# JL2.net
KiCad netlist of a schematic drawn in Altium Designer
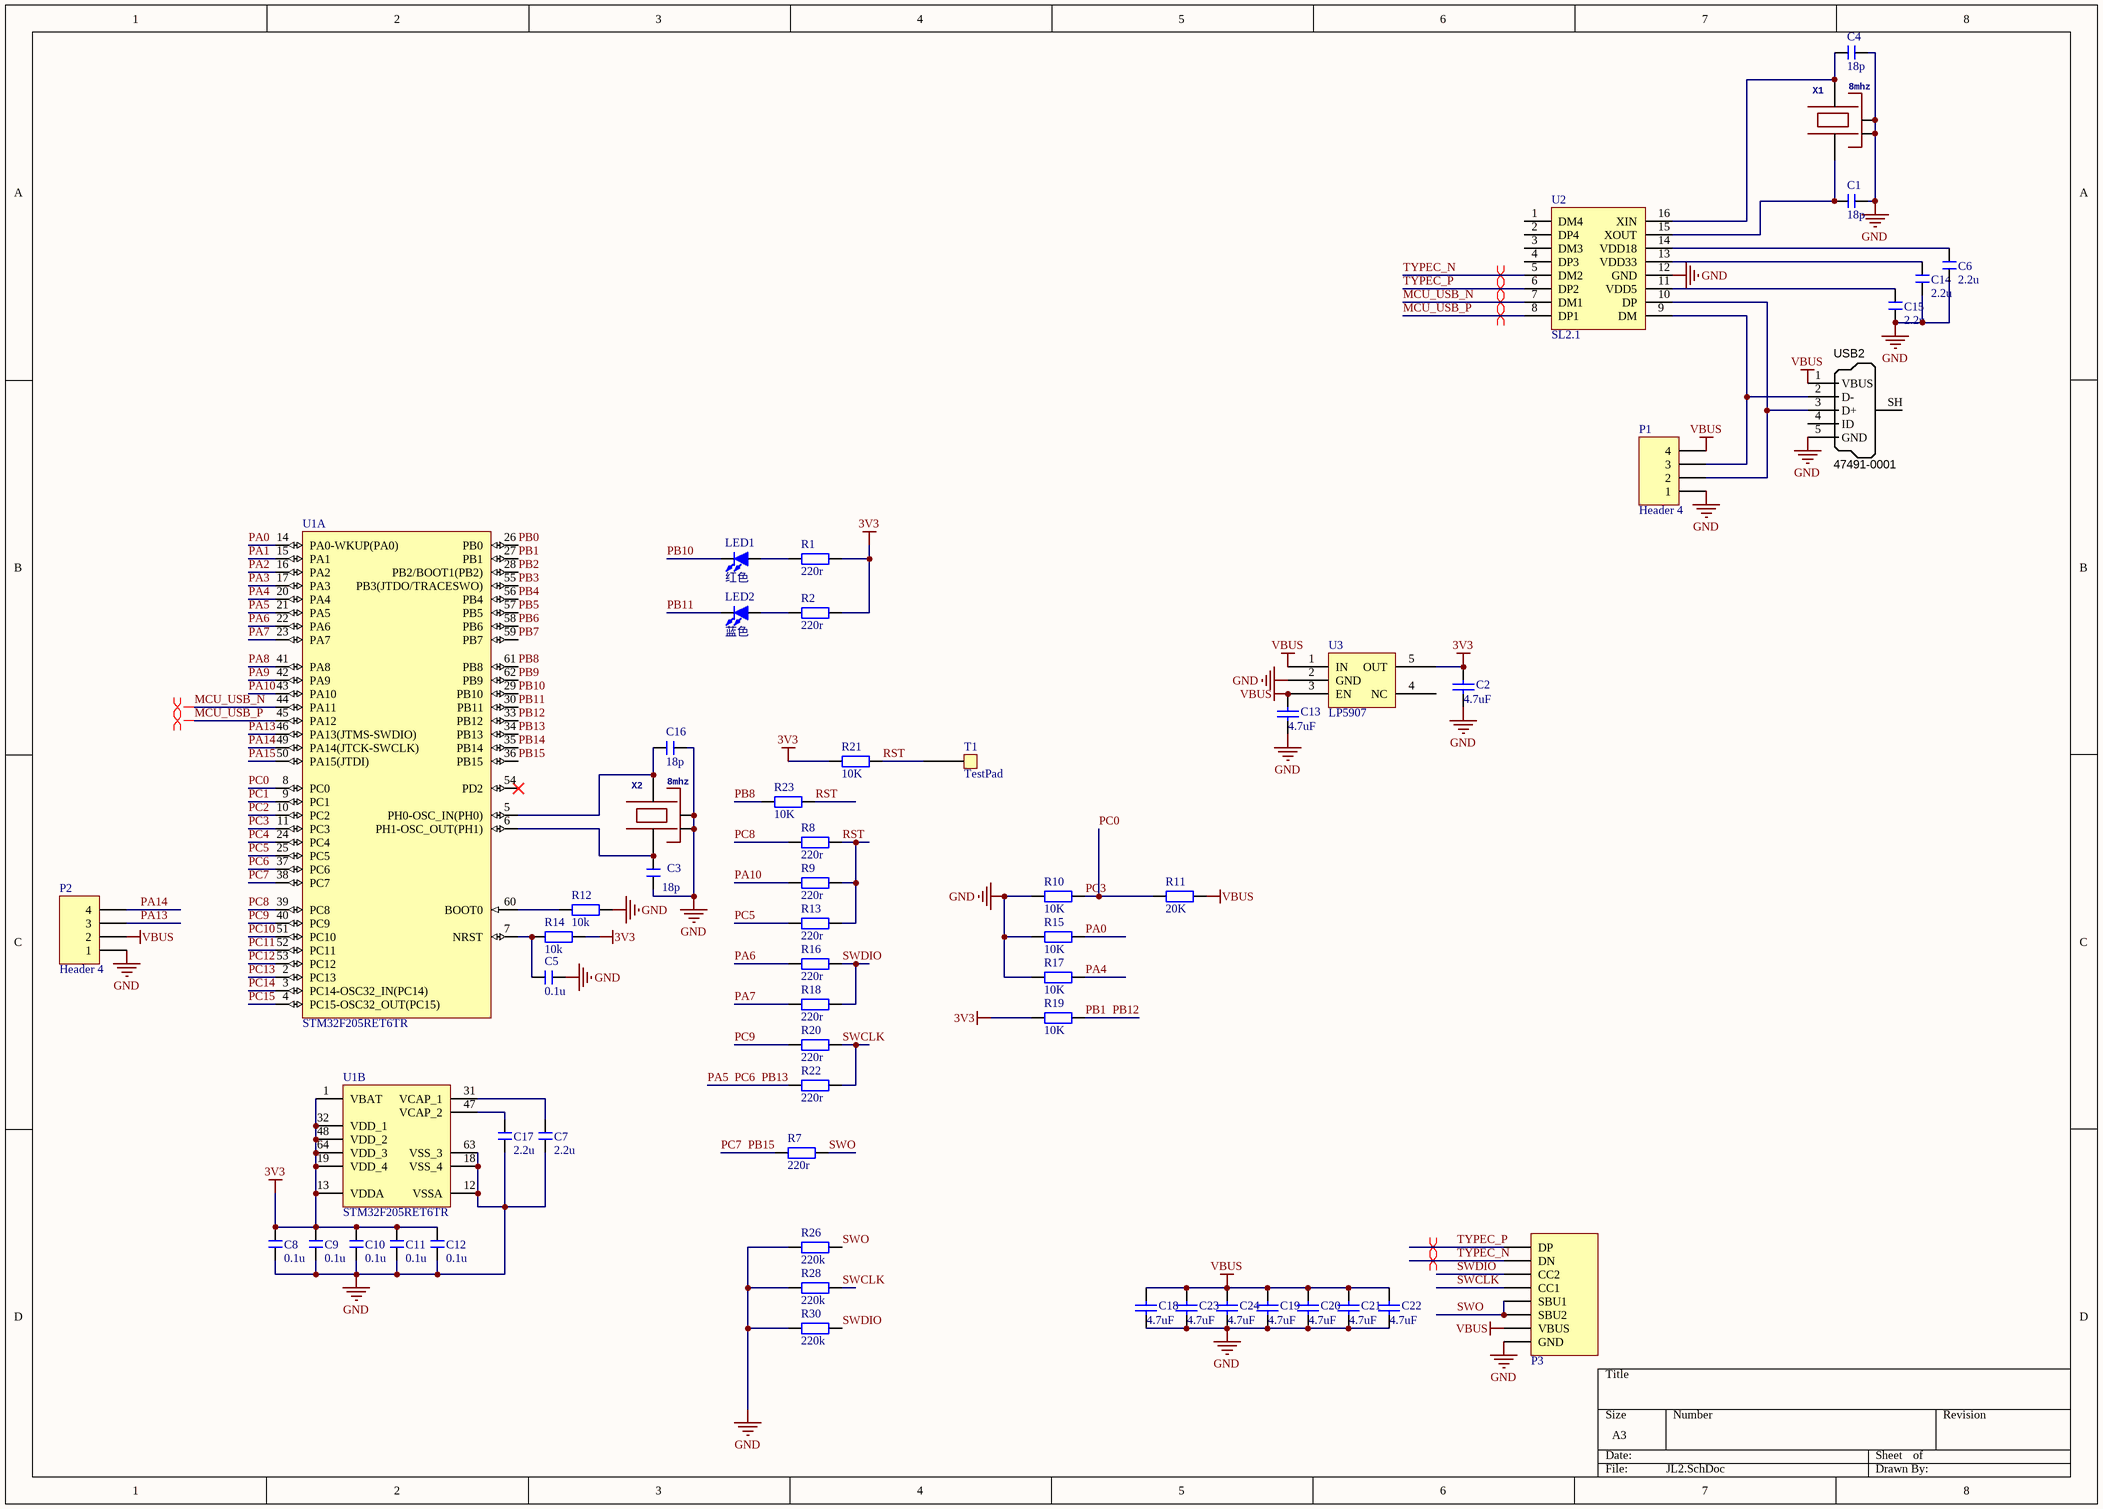
[diagram p0: JL2.SchDoc]

(export (version "E")
  (design (tool "Eeschema 10.0.6"))
  (components
    (comp (ref "C1")
      (value "18p")
      (footprint "0402")
      (description "无极性贴片电容")
      (fields (field (name "版权归属") "黎明电子style"))
      (libsource (lib "MyComponent") (part "C"))
    )
    (comp (ref "C2")
      (value "4.7uF")
      (footprint "0603")
      (description "Capacitor")
      (fields (field (name "PUBLISHER") "Altium Limited"))
      (libsource (lib "RTC6705") (part "Cap"))
    )
    (comp (ref "C3")
      (value "18p")
      (footprint "0402")
      (description "无极性贴片电容")
      (fields (field (name "版权归属") "黎明电子style"))
      (libsource (lib "MyComponent") (part "C"))
    )
    (comp (ref "C4")
      (value "18p")
      (footprint "0402")
      (description "无极性贴片电容")
      (fields (field (name "版权归属") "黎明电子style"))
      (libsource (lib "MyComponent") (part "C"))
    )
    (comp (ref "C5")
      (value "0.1u")
      (footprint "0402")
      (description "无极性贴片电容")
      (fields (field (name "版权归属") "黎明电子style"))
      (libsource (lib "MyComponent") (part "C"))
    )
    (comp (ref "C6")
      (value "2.2u")
      (footprint "0603")
      (description "无极性贴片电容")
      (fields (field (name "版权归属") "黎明电子style"))
      (libsource (lib "MyComponent") (part "C"))
    )
    (comp (ref "C7")
      (value "2.2u")
      (footprint "0603")
      (description "无极性贴片电容")
      (fields (field (name "版权归属") "黎明电子style"))
      (libsource (lib "MyComponent") (part "C"))
    )
    (comp (ref "C8")
      (value "0.1u")
      (footprint "0402")
      (description "无极性贴片电容")
      (fields (field (name "版权归属") "黎明电子style"))
      (libsource (lib "MyComponent") (part "C"))
    )
    (comp (ref "C9")
      (value "0.1u")
      (footprint "0402")
      (description "无极性贴片电容")
      (fields (field (name "版权归属") "黎明电子style"))
      (libsource (lib "MyComponent") (part "C"))
    )
    (comp (ref "C10")
      (value "0.1u")
      (footprint "0402")
      (description "无极性贴片电容")
      (fields (field (name "版权归属") "黎明电子style"))
      (libsource (lib "MyComponent") (part "C"))
    )
    (comp (ref "C11")
      (value "0.1u")
      (footprint "0402")
      (description "无极性贴片电容")
      (fields (field (name "版权归属") "黎明电子style"))
      (libsource (lib "MyComponent") (part "C"))
    )
    (comp (ref "C12")
      (value "0.1u")
      (footprint "0402")
      (description "无极性贴片电容")
      (fields (field (name "版权归属") "黎明电子style"))
      (libsource (lib "MyComponent") (part "C"))
    )
    (comp (ref "C13")
      (value "4.7uF")
      (footprint "0603")
      (description "Capacitor")
      (fields (field (name "PUBLISHER") "Altium Limited"))
      (libsource (lib "RTC6705") (part "Cap"))
    )
    (comp (ref "C14")
      (value "2.2u")
      (footprint "0603")
      (description "无极性贴片电容")
      (fields (field (name "版权归属") "黎明电子style"))
      (libsource (lib "MyComponent") (part "C"))
    )
    (comp (ref "C15")
      (value "2.2u")
      (footprint "0603")
      (description "无极性贴片电容")
      (fields (field (name "版权归属") "黎明电子style"))
      (libsource (lib "MyComponent") (part "C"))
    )
    (comp (ref "C16")
      (value "18p")
      (footprint "0402")
      (description "无极性贴片电容")
      (fields (field (name "版权归属") "黎明电子style"))
      (libsource (lib "MyComponent") (part "C"))
    )
    (comp (ref "C17")
      (value "2.2u")
      (footprint "0603")
      (description "无极性贴片电容")
      (fields (field (name "版权归属") "黎明电子style"))
      (libsource (lib "MyComponent") (part "C"))
    )
    (comp (ref "C18")
      (value "4.7uF")
      (footprint "0603")
      (description "Capacitor")
      (fields (field (name "PUBLISHER") "Altium Limited"))
      (libsource (lib "RTC6705") (part "Cap"))
    )
    (comp (ref "C19")
      (value "4.7uF")
      (footprint "0603")
      (description "Capacitor")
      (fields (field (name "PUBLISHER") "Altium Limited"))
      (libsource (lib "RTC6705") (part "Cap"))
    )
    (comp (ref "C20")
      (value "4.7uF")
      (footprint "0603")
      (description "Capacitor")
      (fields (field (name "PUBLISHER") "Altium Limited"))
      (libsource (lib "RTC6705") (part "Cap"))
    )
    (comp (ref "C21")
      (value "4.7uF")
      (footprint "0603")
      (description "Capacitor")
      (fields (field (name "PUBLISHER") "Altium Limited"))
      (libsource (lib "RTC6705") (part "Cap"))
    )
    (comp (ref "C22")
      (value "4.7uF")
      (footprint "0603")
      (description "Capacitor")
      (fields (field (name "PUBLISHER") "Altium Limited"))
      (libsource (lib "RTC6705") (part "Cap"))
    )
    (comp (ref "C23")
      (value "4.7uF")
      (footprint "0603")
      (description "Capacitor")
      (fields (field (name "PUBLISHER") "Altium Limited"))
      (libsource (lib "RTC6705") (part "Cap"))
    )
    (comp (ref "C24")
      (value "4.7uF")
      (footprint "0603")
      (description "Capacitor")
      (fields (field (name "PUBLISHER") "Altium Limited"))
      (libsource (lib "RTC6705") (part "Cap"))
    )
    (comp (ref "LED1")
      (value "红色")
      (footprint "0603")
      (description "贴片LED")
      (fields (field (name "版权归属") "黎明电子style"))
      (libsource (lib "MyComponent") (part "LED-SMD"))
    )
    (comp (ref "LED2")
      (value "蓝色")
      (footprint "0603")
      (description "贴片LED")
      (fields (field (name "版权归属") "黎明电子style"))
      (libsource (lib "MyComponent") (part "LED-SMD"))
    )
    (comp (ref "P1")
      (value "Header 4")
      (footprint "HDR1X4")
      (description "Header, 4-Pin")
      (fields (field (name "PUBLISHER") "Altium Limited"))
      (libsource (lib "Miscellaneous Connectors") (part "Header 4"))
    )
    (comp (ref "P2")
      (value "Header 4")
      (footprint "HDR1X4")
      (description "Header, 4-Pin")
      (fields (field (name "PUBLISHER") "Altium Limited"))
      (libsource (lib "Miscellaneous Connectors") (part "Header 4"))
    )
    (comp (ref "P3") (value "USBC") (footprint "USBTC") (libsource (lib "link") (part "USBC")))
    (comp (ref "R1")
      (value "220r")
      (footprint "0402")
      (description "贴片电阻")
      (fields (field (name "版权归属") "黎明电子style"))
      (libsource (lib "MyComponent") (part "R"))
    )
    (comp (ref "R2")
      (value "220r")
      (footprint "0402")
      (description "贴片电阻")
      (fields (field (name "版权归属") "黎明电子style"))
      (libsource (lib "MyComponent") (part "R"))
    )
    (comp (ref "R7")
      (value "220r")
      (footprint "0402")
      (description "贴片电阻")
      (fields (field (name "版权归属") "黎明电子style"))
      (libsource (lib "MyComponent") (part "R"))
    )
    (comp (ref "R8")
      (value "220r")
      (footprint "0402")
      (description "贴片电阻")
      (fields (field (name "版权归属") "黎明电子style"))
      (libsource (lib "MyComponent") (part "R"))
    )
    (comp (ref "R9")
      (value "220r")
      (footprint "0402")
      (description "贴片电阻")
      (fields (field (name "版权归属") "黎明电子style"))
      (libsource (lib "MyComponent") (part "R"))
    )
    (comp (ref "R10")
      (value "10K")
      (footprint "0402")
      (description "贴片电阻")
      (fields (field (name "版权归属") "黎明电子style"))
      (libsource (lib "MyComponent") (part "R"))
    )
    (comp (ref "R11")
      (value "20K")
      (footprint "0402")
      (description "贴片电阻")
      (fields (field (name "版权归属") "黎明电子style"))
      (libsource (lib "MyComponent") (part "R"))
    )
    (comp (ref "R12")
      (value "10k")
      (footprint "0402")
      (description "贴片电阻")
      (fields (field (name "版权归属") "黎明电子style"))
      (libsource (lib "MyComponent") (part "R"))
    )
    (comp (ref "R13")
      (value "220r")
      (footprint "0402")
      (description "贴片电阻")
      (fields (field (name "版权归属") "黎明电子style"))
      (libsource (lib "MyComponent") (part "R"))
    )
    (comp (ref "R14")
      (value "10k")
      (footprint "0402")
      (description "贴片电阻")
      (fields (field (name "版权归属") "黎明电子style"))
      (libsource (lib "MyComponent") (part "R"))
    )
    (comp (ref "R15")
      (value "10K")
      (footprint "0402")
      (description "贴片电阻")
      (fields (field (name "版权归属") "黎明电子style"))
      (libsource (lib "MyComponent") (part "R"))
    )
    (comp (ref "R16")
      (value "220r")
      (footprint "0402")
      (description "贴片电阻")
      (fields (field (name "版权归属") "黎明电子style"))
      (libsource (lib "MyComponent") (part "R"))
    )
    (comp (ref "R17")
      (value "10K")
      (footprint "0402")
      (description "贴片电阻")
      (fields (field (name "版权归属") "黎明电子style"))
      (libsource (lib "MyComponent") (part "R"))
    )
    (comp (ref "R18")
      (value "220r")
      (footprint "0402")
      (description "贴片电阻")
      (fields (field (name "版权归属") "黎明电子style"))
      (libsource (lib "MyComponent") (part "R"))
    )
    (comp (ref "R19")
      (value "10K")
      (footprint "0402")
      (description "贴片电阻")
      (fields (field (name "版权归属") "黎明电子style"))
      (libsource (lib "MyComponent") (part "R"))
    )
    (comp (ref "R20")
      (value "220r")
      (footprint "0402")
      (description "贴片电阻")
      (fields (field (name "版权归属") "黎明电子style"))
      (libsource (lib "MyComponent") (part "R"))
    )
    (comp (ref "R21")
      (value "10K")
      (footprint "0402")
      (description "贴片电阻")
      (fields (field (name "版权归属") "黎明电子style"))
      (libsource (lib "MyComponent") (part "R"))
    )
    (comp (ref "R22")
      (value "220r")
      (footprint "0402")
      (description "贴片电阻")
      (fields (field (name "版权归属") "黎明电子style"))
      (libsource (lib "MyComponent") (part "R"))
    )
    (comp (ref "R23")
      (value "10K")
      (footprint "0402")
      (description "贴片电阻")
      (fields (field (name "版权归属") "黎明电子style"))
      (libsource (lib "MyComponent") (part "R"))
    )
    (comp (ref "R26")
      (value "220k")
      (footprint "0402")
      (description "贴片电阻")
      (fields (field (name "版权归属") "黎明电子style"))
      (libsource (lib "MyComponent") (part "R"))
    )
    (comp (ref "R28")
      (value "220k")
      (footprint "0402")
      (description "贴片电阻")
      (fields (field (name "版权归属") "黎明电子style"))
      (libsource (lib "MyComponent") (part "R"))
    )
    (comp (ref "R30")
      (value "220k")
      (footprint "0402")
      (description "贴片电阻")
      (fields (field (name "版权归属") "黎明电子style"))
      (libsource (lib "MyComponent") (part "R"))
    )
    (comp (ref "T1") (value "TestPad") (footprint "TestPad - 1mm") (libsource (lib "sch") (part "TestPad")))
    (comp (ref "U1")
      (value "STM32F205RET6TR")
      (footprint "LQFP64 10X10_L")
      (libsource (lib "STMicroelectronics STM32") (part "STM32F205RET6TR"))
    )
    (comp (ref "U2") (value "SL2.1") (footprint "SOP16") (libsource (lib "link") (part "SL2.1")))
    (comp (ref "U3") (value "LP5907") (footprint "SOT23-5") (libsource (lib "RTC6705") (part "LP5907")))
    (comp (ref "USB2")
      (value "USB Micro Type B")
      (footprint "MICRO-YZX")
      (description "Connector SMD USB Micro Type B middle mount")
      (fields (field (name "MANUFACTURER PART NUMBER 1") "47491-0001"))
      (libsource (lib "PBL - Connectors") (part "USB_Micro_TypeB"))
    )
    (comp (ref "X1")
      (value "8mhz")
      (footprint "OSCILLATOR-3.2X2.5")
      (description "Crystal Oscillator in 3.2x2.5 SMD")
      (libsource (lib "sch") (part "OSCILLATOR-3.2X2.5"))
    )
    (comp (ref "X2")
      (value "8mhz")
      (footprint "OSCILLATOR-3.2X2.5")
      (description "Crystal Oscillator in 3.2x2.5 SMD")
      (libsource (lib "sch") (part "OSCILLATOR-3.2X2.5"))
    )
  )
  (nets
    (net (code "1") (name "/MCU_USB_N") (class "Default")
      (node (ref "U1") (pin "44") (pinfunction "PA11_44") (pintype "bidirectional"))
      (node (ref "U2") (pin "7") (pinfunction "DM1_7") (pintype "passive"))
    )
    (net (code "2") (name "/MCU_USB_P") (class "Default")
      (node (ref "U1") (pin "45") (pinfunction "PA12_45") (pintype "bidirectional"))
      (node (ref "U2") (pin "8") (pinfunction "DP1_8") (pintype "passive"))
    )
    (net (code "3") (name "/PA0") (class "Default")
      (node (ref "R15") (pin "1") (pinfunction "1_1") (pintype "passive"))
      (node (ref "U1") (pin "14") (pinfunction "PA0-WKUP(PA0)_14") (pintype "bidirectional"))
    )
    (net (code "4") (name "/PA1") (class "Default")
      (node (ref "U1") (pin "15") (pinfunction "PA1_15") (pintype "bidirectional"))
    )
    (net (code "5") (name "/PA2") (class "Default")
      (node (ref "U1") (pin "16") (pinfunction "PA2_16") (pintype "bidirectional"))
    )
    (net (code "6") (name "/PA3") (class "Default")
      (node (ref "U1") (pin "17") (pinfunction "PA3_17") (pintype "bidirectional"))
    )
    (net (code "7") (name "/PA4") (class "Default")
      (node (ref "R17") (pin "1") (pinfunction "1_1") (pintype "passive"))
      (node (ref "U1") (pin "20") (pinfunction "PA4_20") (pintype "bidirectional"))
    )
    (net (code "8") (name "/PA5") (class "Default")
      (node (ref "R22") (pin "2") (pinfunction "2_2") (pintype "passive"))
      (node (ref "U1") (pin "21") (pinfunction "PA5_21") (pintype "bidirectional"))
      (node (ref "U1") (pin "34") (pinfunction "PB13_34") (pintype "bidirectional"))
      (node (ref "U1") (pin "37") (pinfunction "PC6_37") (pintype "bidirectional"))
    )
    (net (code "9") (name "/PA6") (class "Default")
      (node (ref "R16") (pin "2") (pinfunction "2_2") (pintype "passive"))
      (node (ref "U1") (pin "22") (pinfunction "PA6_22") (pintype "bidirectional"))
    )
    (net (code "10") (name "/PA7") (class "Default")
      (node (ref "R18") (pin "2") (pinfunction "2_2") (pintype "passive"))
      (node (ref "U1") (pin "23") (pinfunction "PA7_23") (pintype "bidirectional"))
    )
    (net (code "11") (name "/PA8") (class "Default")
      (node (ref "U1") (pin "41") (pinfunction "PA8_41") (pintype "bidirectional"))
    )
    (net (code "12") (name "/PA9") (class "Default")
      (node (ref "U1") (pin "42") (pinfunction "PA9_42") (pintype "bidirectional"))
    )
    (net (code "13") (name "/PA10") (class "Default")
      (node (ref "R9") (pin "2") (pinfunction "2_2") (pintype "passive"))
      (node (ref "U1") (pin "43") (pinfunction "PA10_43") (pintype "bidirectional"))
    )
    (net (code "14") (name "/PA13") (class "Default")
      (node (ref "P2") (pin "3") (pinfunction "3_3") (pintype "passive"))
      (node (ref "U1") (pin "46") (pinfunction "PA13(JTMS-SWDIO)_46") (pintype "bidirectional"))
    )
    (net (code "15") (name "/PA14") (class "Default")
      (node (ref "P2") (pin "4") (pinfunction "4_4") (pintype "passive"))
      (node (ref "U1") (pin "49") (pinfunction "PA14(JTCK-SWCLK)_49") (pintype "bidirectional"))
    )
    (net (code "16") (name "/PA15") (class "Default")
      (node (ref "U1") (pin "50") (pinfunction "PA15(JTDI)_50") (pintype "bidirectional"))
    )
    (net (code "17") (name "/PB0") (class "Default")
      (node (ref "U1") (pin "26") (pinfunction "PB0_26") (pintype "bidirectional"))
    )
    (net (code "18") (name "/PB1") (class "Default")
      (node (ref "R19") (pin "1") (pinfunction "1_1") (pintype "passive"))
      (node (ref "U1") (pin "27") (pinfunction "PB1_27") (pintype "bidirectional"))
      (node (ref "U1") (pin "33") (pinfunction "PB12_33") (pintype "bidirectional"))
    )
    (net (code "19") (name "/PB2") (class "Default")
      (node (ref "U1") (pin "28") (pinfunction "PB2/BOOT1(PB2)_28") (pintype "bidirectional"))
    )
    (net (code "20") (name "/PB3") (class "Default")
      (node (ref "U1") (pin "55") (pinfunction "PB3(JTDO/TRACESWO)_55") (pintype "bidirectional"))
    )
    (net (code "21") (name "/PB4") (class "Default")
      (node (ref "U1") (pin "56") (pinfunction "PB4_56") (pintype "bidirectional"))
    )
    (net (code "22") (name "/PB5") (class "Default")
      (node (ref "U1") (pin "57") (pinfunction "PB5_57") (pintype "bidirectional"))
    )
    (net (code "23") (name "/PB6") (class "Default")
      (node (ref "U1") (pin "58") (pinfunction "PB6_58") (pintype "bidirectional"))
    )
    (net (code "24") (name "/PB7") (class "Default")
      (node (ref "U1") (pin "59") (pinfunction "PB7_59") (pintype "bidirectional"))
    )
    (net (code "25") (name "/PB8") (class "Default")
      (node (ref "R23") (pin "2") (pinfunction "2_2") (pintype "passive"))
      (node (ref "U1") (pin "61") (pinfunction "PB8_61") (pintype "bidirectional"))
    )
    (net (code "26") (name "/PB9") (class "Default")
      (node (ref "U1") (pin "62") (pinfunction "PB9_62") (pintype "bidirectional"))
    )
    (net (code "27") (name "/PB10") (class "Default")
      (node (ref "LED1") (pin "2") (pinfunction "K_2") (pintype "passive"))
      (node (ref "U1") (pin "29") (pinfunction "PB10_29") (pintype "bidirectional"))
    )
    (net (code "28") (name "/PB11") (class "Default")
      (node (ref "LED2") (pin "2") (pinfunction "K_2") (pintype "passive"))
      (node (ref "U1") (pin "30") (pinfunction "PB11_30") (pintype "bidirectional"))
    )
    (net (code "29") (name "/PB14") (class "Default")
      (node (ref "U1") (pin "35") (pinfunction "PB14_35") (pintype "bidirectional"))
    )
    (net (code "30") (name "/PB15") (class "Default")
      (node (ref "R7") (pin "2") (pinfunction "2_2") (pintype "passive"))
      (node (ref "U1") (pin "36") (pinfunction "PB15_36") (pintype "bidirectional"))
      (node (ref "U1") (pin "38") (pinfunction "PC7_38") (pintype "bidirectional"))
    )
    (net (code "31") (name "/PC0") (class "Default")
      (node (ref "R10") (pin "1") (pinfunction "1_1") (pintype "passive"))
      (node (ref "R11") (pin "2") (pinfunction "2_2") (pintype "passive"))
      (node (ref "U1") (pin "11") (pinfunction "PC3_11") (pintype "bidirectional"))
      (node (ref "U1") (pin "8") (pinfunction "PC0_8") (pintype "bidirectional"))
    )
    (net (code "32") (name "/PC1") (class "Default")
      (node (ref "U1") (pin "9") (pinfunction "PC1_9") (pintype "bidirectional"))
    )
    (net (code "33") (name "/PC2") (class "Default")
      (node (ref "U1") (pin "10") (pinfunction "PC2_10") (pintype "bidirectional"))
    )
    (net (code "34") (name "/PC4") (class "Default")
      (node (ref "U1") (pin "24") (pinfunction "PC4_24") (pintype "bidirectional"))
    )
    (net (code "35") (name "/PC5") (class "Default")
      (node (ref "R13") (pin "2") (pinfunction "2_2") (pintype "passive"))
      (node (ref "U1") (pin "25") (pinfunction "PC5_25") (pintype "bidirectional"))
    )
    (net (code "36") (name "/PC8") (class "Default")
      (node (ref "R8") (pin "2") (pinfunction "2_2") (pintype "passive"))
      (node (ref "U1") (pin "39") (pinfunction "PC8_39") (pintype "bidirectional"))
    )
    (net (code "37") (name "/PC9") (class "Default")
      (node (ref "R20") (pin "2") (pinfunction "2_2") (pintype "passive"))
      (node (ref "U1") (pin "40") (pinfunction "PC9_40") (pintype "bidirectional"))
    )
    (net (code "38") (name "/PC10") (class "Default")
      (node (ref "U1") (pin "51") (pinfunction "PC10_51") (pintype "bidirectional"))
    )
    (net (code "39") (name "/PC11") (class "Default")
      (node (ref "U1") (pin "52") (pinfunction "PC11_52") (pintype "bidirectional"))
    )
    (net (code "40") (name "/PC12") (class "Default")
      (node (ref "U1") (pin "53") (pinfunction "PC12_53") (pintype "bidirectional"))
    )
    (net (code "41") (name "/PC13") (class "Default")
      (node (ref "U1") (pin "2") (pinfunction "PC13_2") (pintype "bidirectional"))
    )
    (net (code "42") (name "/PC14") (class "Default")
      (node (ref "U1") (pin "3") (pinfunction "PC14-OSC32_IN(PC14)_3") (pintype "bidirectional"))
    )
    (net (code "43") (name "/PC15") (class "Default")
      (node (ref "U1") (pin "4") (pinfunction "PC15-OSC32_OUT(PC15)_4") (pintype "bidirectional"))
    )
    (net (code "44") (name "/RST") (class "Default")
      (node (ref "R13") (pin "1") (pinfunction "1_1") (pintype "passive"))
      (node (ref "R21") (pin "1") (pinfunction "1_1") (pintype "passive"))
      (node (ref "R23") (pin "1") (pinfunction "1_1") (pintype "passive"))
      (node (ref "R8") (pin "1") (pinfunction "1_1") (pintype "passive"))
      (node (ref "R9") (pin "1") (pinfunction "1_1") (pintype "passive"))
      (node (ref "T1") (pin "1") (pinfunction "3_1") (pintype "passive"))
    )
    (net (code "45") (name "/SWCLK") (class "Default")
      (node (ref "P3") (pin "CC1") (pinfunction "CC1_CC1") (pintype "passive"))
      (node (ref "R20") (pin "1") (pinfunction "1_1") (pintype "passive"))
      (node (ref "R22") (pin "1") (pinfunction "1_1") (pintype "passive"))
      (node (ref "R28") (pin "1") (pinfunction "1_1") (pintype "passive"))
    )
    (net (code "46") (name "/SWDIO") (class "Default")
      (node (ref "P3") (pin "CC2") (pinfunction "CC2_CC2") (pintype "passive"))
      (node (ref "R16") (pin "1") (pinfunction "1_1") (pintype "passive"))
      (node (ref "R18") (pin "1") (pinfunction "1_1") (pintype "passive"))
      (node (ref "R30") (pin "1") (pinfunction "1_1") (pintype "passive"))
    )
    (net (code "47") (name "/SWO") (class "Default")
      (node (ref "P3") (pin "SBU1") (pinfunction "SBU1_SBU1") (pintype "passive"))
      (node (ref "P3") (pin "SBU2") (pinfunction "SBU2_SBU2") (pintype "passive"))
      (node (ref "R26") (pin "1") (pinfunction "1_1") (pintype "passive"))
      (node (ref "R7") (pin "1") (pinfunction "1_1") (pintype "passive"))
    )
    (net (code "48") (name "/TYPEC_N") (class "Default")
      (node (ref "P3") (pin "DN") (pinfunction "DN_DN") (pintype "passive"))
      (node (ref "U2") (pin "5") (pinfunction "DM2_5") (pintype "passive"))
    )
    (net (code "49") (name "/TYPEC_P") (class "Default")
      (node (ref "P3") (pin "DP") (pinfunction "DP_DP") (pintype "passive"))
      (node (ref "U2") (pin "6") (pinfunction "DP2_6") (pintype "passive"))
    )
    (net (code "50") (name "3V3") (class "Default")
      (node (ref "C10") (pin "2") (pinfunction "2_2") (pintype "passive"))
      (node (ref "C11") (pin "2") (pinfunction "2_2") (pintype "passive"))
      (node (ref "C12") (pin "2") (pinfunction "2_2") (pintype "passive"))
      (node (ref "C2") (pin "2") (pinfunction "2_2") (pintype "passive"))
      (node (ref "C8") (pin "2") (pinfunction "2_2") (pintype "passive"))
      (node (ref "C9") (pin "2") (pinfunction "2_2") (pintype "passive"))
      (node (ref "R1") (pin "1") (pinfunction "1_1") (pintype "passive"))
      (node (ref "R14") (pin "1") (pinfunction "1_1") (pintype "passive"))
      (node (ref "R19") (pin "2") (pinfunction "2_2") (pintype "passive"))
      (node (ref "R2") (pin "1") (pinfunction "1_1") (pintype "passive"))
      (node (ref "R21") (pin "2") (pinfunction "2_2") (pintype "passive"))
      (node (ref "U1") (pin "1") (pinfunction "VBAT_1") (pintype "power_in"))
      (node (ref "U1") (pin "13") (pinfunction "VDDA_13") (pintype "power_in"))
      (node (ref "U1") (pin "19") (pinfunction "VDD_4_19") (pintype "power_in"))
      (node (ref "U1") (pin "32") (pinfunction "VDD_1_32") (pintype "power_in"))
      (node (ref "U1") (pin "48") (pinfunction "VDD_2_48") (pintype "power_in"))
      (node (ref "U1") (pin "64") (pinfunction "VDD_3_64") (pintype "power_in"))
      (node (ref "U3") (pin "5") (pinfunction "OUT_5") (pintype "passive"))
    )
    (net (code "51") (name "GND") (class "Default")
      (node (ref "C1") (pin "2") (pinfunction "2_2") (pintype "passive"))
      (node (ref "C10") (pin "1") (pinfunction "1_1") (pintype "passive"))
      (node (ref "C11") (pin "1") (pinfunction "1_1") (pintype "passive"))
      (node (ref "C12") (pin "1") (pinfunction "1_1") (pintype "passive"))
      (node (ref "C13") (pin "1") (pinfunction "1_1") (pintype "passive"))
      (node (ref "C14") (pin "1") (pinfunction "1_1") (pintype "passive"))
      (node (ref "C15") (pin "1") (pinfunction "1_1") (pintype "passive"))
      (node (ref "C16") (pin "2") (pinfunction "2_2") (pintype "passive"))
      (node (ref "C17") (pin "1") (pinfunction "1_1") (pintype "passive"))
      (node (ref "C18") (pin "1") (pinfunction "1_1") (pintype "passive"))
      (node (ref "C19") (pin "1") (pinfunction "1_1") (pintype "passive"))
      (node (ref "C2") (pin "1") (pinfunction "1_1") (pintype "passive"))
      (node (ref "C20") (pin "1") (pinfunction "1_1") (pintype "passive"))
      (node (ref "C21") (pin "1") (pinfunction "1_1") (pintype "passive"))
      (node (ref "C22") (pin "1") (pinfunction "1_1") (pintype "passive"))
      (node (ref "C23") (pin "1") (pinfunction "1_1") (pintype "passive"))
      (node (ref "C24") (pin "1") (pinfunction "1_1") (pintype "passive"))
      (node (ref "C3") (pin "2") (pinfunction "2_2") (pintype "passive"))
      (node (ref "C4") (pin "2") (pinfunction "2_2") (pintype "passive"))
      (node (ref "C5") (pin "1") (pinfunction "1_1") (pintype "passive"))
      (node (ref "C6") (pin "1") (pinfunction "1_1") (pintype "passive"))
      (node (ref "C7") (pin "1") (pinfunction "1_1") (pintype "passive"))
      (node (ref "C8") (pin "1") (pinfunction "1_1") (pintype "passive"))
      (node (ref "C9") (pin "1") (pinfunction "1_1") (pintype "passive"))
      (node (ref "P1") (pin "1") (pinfunction "1_1") (pintype "passive"))
      (node (ref "P2") (pin "1") (pinfunction "1_1") (pintype "passive"))
      (node (ref "P3") (pin "GND") (pinfunction "GND_GND") (pintype "passive"))
      (node (ref "R10") (pin "2") (pinfunction "2_2") (pintype "passive"))
      (node (ref "R12") (pin "1") (pinfunction "1_1") (pintype "passive"))
      (node (ref "R15") (pin "2") (pinfunction "2_2") (pintype "passive"))
      (node (ref "R17") (pin "2") (pinfunction "2_2") (pintype "passive"))
      (node (ref "R26") (pin "2") (pinfunction "2_2") (pintype "passive"))
      (node (ref "R28") (pin "2") (pinfunction "2_2") (pintype "passive"))
      (node (ref "R30") (pin "2") (pinfunction "2_2") (pintype "passive"))
      (node (ref "U1") (pin "12") (pinfunction "VSSA_12") (pintype "power_in"))
      (node (ref "U1") (pin "18") (pinfunction "VSS_4_18") (pintype "power_in"))
      (node (ref "U1") (pin "63") (pinfunction "VSS_3_63") (pintype "power_in"))
      (node (ref "U2") (pin "12") (pinfunction "GND_12") (pintype "passive"))
      (node (ref "U3") (pin "2") (pinfunction "GND_2") (pintype "passive"))
      (node (ref "USB2") (pin "5") (pinfunction "GND_5") (pintype "passive"))
      (node (ref "X1") (pin "2") (pinfunction "NC_2_2") (pintype "open_emitter"))
      (node (ref "X1") (pin "4") (pinfunction "NC_4_4") (pintype "open_emitter"))
      (node (ref "X2") (pin "2") (pinfunction "NC_2_2") (pintype "open_emitter"))
      (node (ref "X2") (pin "4") (pinfunction "NC_4_4") (pintype "open_emitter"))
    )
    (net (code "52") (name "Net-(LED1-A)") (class "Default")
      (node (ref "LED1") (pin "1") (pinfunction "A_1") (pintype "passive"))
      (node (ref "R1") (pin "2") (pinfunction "2_2") (pintype "passive"))
    )
    (net (code "53") (name "Net-(LED2-A)") (class "Default")
      (node (ref "LED2") (pin "1") (pinfunction "A_1") (pintype "passive"))
      (node (ref "R2") (pin "2") (pinfunction "2_2") (pintype "passive"))
    )
    (net (code "54") (name "Net-(U1A-BOOT0)") (class "Default")
      (node (ref "R12") (pin "2") (pinfunction "2_2") (pintype "passive"))
      (node (ref "U1") (pin "60") (pinfunction "BOOT0_60") (pintype "input"))
    )
    (net (code "55") (name "Net-(U1A-NRST)") (class "Default")
      (node (ref "C5") (pin "2") (pinfunction "2_2") (pintype "passive"))
      (node (ref "R14") (pin "2") (pinfunction "2_2") (pintype "passive"))
      (node (ref "U1") (pin "7") (pinfunction "NRST_7") (pintype "bidirectional"))
    )
    (net (code "56") (name "Net-(U1A-PH0-OSC_IN(PH0))") (class "Default")
      (node (ref "C16") (pin "1") (pinfunction "1_1") (pintype "passive"))
      (node (ref "U1") (pin "5") (pinfunction "PH0-OSC_IN(PH0)_5") (pintype "bidirectional"))
      (node (ref "X2") (pin "3") (pinfunction "3_3") (pintype "passive"))
    )
    (net (code "57") (name "Net-(U1A-PH1-OSC_OUT(PH1))") (class "Default")
      (node (ref "C3") (pin "1") (pinfunction "1_1") (pintype "passive"))
      (node (ref "U1") (pin "6") (pinfunction "PH1-OSC_OUT(PH1)_6") (pintype "bidirectional"))
      (node (ref "X2") (pin "1") (pinfunction "1_1") (pintype "passive"))
    )
    (net (code "58") (name "Net-(U1B-VCAP_1)") (class "Default")
      (node (ref "C7") (pin "2") (pinfunction "2_2") (pintype "passive"))
      (node (ref "U1") (pin "31") (pinfunction "VCAP_1_31") (pintype "power_in"))
    )
    (net (code "59") (name "Net-(U1B-VCAP_2)") (class "Default")
      (node (ref "C17") (pin "2") (pinfunction "2_2") (pintype "passive"))
      (node (ref "U1") (pin "47") (pinfunction "VCAP_2_47") (pintype "power_in"))
    )
    (net (code "60") (name "Net-(U2-DM)") (class "Default")
      (node (ref "P1") (pin "3") (pinfunction "3_3") (pintype "passive"))
      (node (ref "U2") (pin "9") (pinfunction "DM_9") (pintype "passive"))
      (node (ref "USB2") (pin "2") (pinfunction "D-_2") (pintype "passive"))
    )
    (net (code "61") (name "Net-(U2-DP)") (class "Default")
      (node (ref "P1") (pin "2") (pinfunction "2_2") (pintype "passive"))
      (node (ref "U2") (pin "10") (pinfunction "DP_10") (pintype "passive"))
      (node (ref "USB2") (pin "3") (pinfunction "D+_3") (pintype "passive"))
    )
    (net (code "62") (name "Net-(U2-VDD5)") (class "Default")
      (node (ref "C15") (pin "2") (pinfunction "2_2") (pintype "passive"))
      (node (ref "U2") (pin "11") (pinfunction "VDD5_11") (pintype "passive"))
    )
    (net (code "63") (name "Net-(U2-VDD18)") (class "Default")
      (node (ref "C6") (pin "2") (pinfunction "2_2") (pintype "passive"))
      (node (ref "U2") (pin "14") (pinfunction "VDD18_14") (pintype "passive"))
    )
    (net (code "64") (name "Net-(U2-VDD33)") (class "Default")
      (node (ref "C14") (pin "2") (pinfunction "2_2") (pintype "passive"))
      (node (ref "U2") (pin "13") (pinfunction "VDD33_13") (pintype "passive"))
    )
    (net (code "65") (name "Net-(U2-XIN)") (class "Default")
      (node (ref "C4") (pin "1") (pinfunction "1_1") (pintype "passive"))
      (node (ref "U2") (pin "16") (pinfunction "XIN_16") (pintype "passive"))
      (node (ref "X1") (pin "3") (pinfunction "3_3") (pintype "passive"))
    )
    (net (code "66") (name "Net-(U2-XOUT)") (class "Default")
      (node (ref "C1") (pin "1") (pinfunction "1_1") (pintype "passive"))
      (node (ref "U2") (pin "15") (pinfunction "XOUT_15") (pintype "passive"))
      (node (ref "X1") (pin "1") (pinfunction "1_1") (pintype "passive"))
    )
    (net (code "67") (name "VBUS") (class "Default")
      (node (ref "C13") (pin "2") (pinfunction "2_2") (pintype "passive"))
      (node (ref "C18") (pin "2") (pinfunction "2_2") (pintype "passive"))
      (node (ref "C19") (pin "2") (pinfunction "2_2") (pintype "passive"))
      (node (ref "C20") (pin "2") (pinfunction "2_2") (pintype "passive"))
      (node (ref "C21") (pin "2") (pinfunction "2_2") (pintype "passive"))
      (node (ref "C22") (pin "2") (pinfunction "2_2") (pintype "passive"))
      (node (ref "C23") (pin "2") (pinfunction "2_2") (pintype "passive"))
      (node (ref "C24") (pin "2") (pinfunction "2_2") (pintype "passive"))
      (node (ref "P1") (pin "4") (pinfunction "4_4") (pintype "passive"))
      (node (ref "P2") (pin "2") (pinfunction "2_2") (pintype "passive"))
      (node (ref "P3") (pin "VBUS") (pinfunction "VBUS_VBUS") (pintype "passive"))
      (node (ref "R11") (pin "1") (pinfunction "1_1") (pintype "passive"))
      (node (ref "U3") (pin "1") (pinfunction "IN_1") (pintype "passive"))
      (node (ref "U3") (pin "3") (pinfunction "EN_3") (pintype "passive"))
      (node (ref "USB2") (pin "1") (pinfunction "VBUS_1") (pintype "passive"))
    )
    (net (code "68") (name "unconnected-(U1A-PD2-Pad54)") (class "Default")
      (node (ref "U1") (pin "54") (pinfunction "PD2_54") (pintype "bidirectional+no_connect"))
    )
    (net (code "69") (name "unconnected-(U2-DM3-Pad3)") (class "Default")
      (node (ref "U2") (pin "3") (pinfunction "DM3_3") (pintype "passive"))
    )
    (net (code "70") (name "unconnected-(U2-DM4-Pad1)") (class "Default")
      (node (ref "U2") (pin "1") (pinfunction "DM4_1") (pintype "passive"))
    )
    (net (code "71") (name "unconnected-(U2-DP3-Pad4)") (class "Default")
      (node (ref "U2") (pin "4") (pinfunction "DP3_4") (pintype "passive"))
    )
    (net (code "72") (name "unconnected-(U2-DP4-Pad2)") (class "Default")
      (node (ref "U2") (pin "2") (pinfunction "DP4_2") (pintype "passive"))
    )
    (net (code "73") (name "unconnected-(U3-NC-Pad4)") (class "Default")
      (node (ref "U3") (pin "4") (pinfunction "NC_4") (pintype "passive"))
    )
    (net (code "74") (name "unconnected-(USB2-ID-Pad4)") (class "Default")
      (node (ref "USB2") (pin "4") (pinfunction "ID_4") (pintype "passive"))
    )
    (net (code "75") (name "unconnected-(USB2-Shell-PadSH)") (class "Default")
      (node (ref "USB2") (pin "SH") (pinfunction "Shell_SH") (pintype "passive"))
    )
  )
)
